# Schematic.net
KiCad netlist of a schematic drawn in Altium Designer
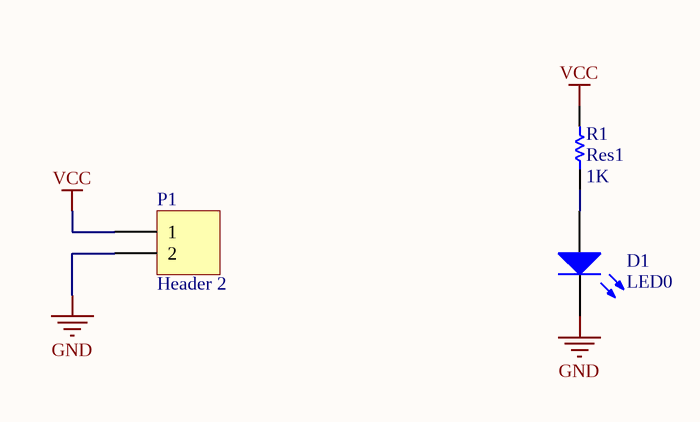
[diagram p0: Schematic.SchDoc]

(export (version "E")
  (design (tool "Eeschema 10.0.6"))
  (components
    (comp (ref "D1")
      (value "LED0")
      (footprint "LED-0")
      (description "Typical INFRARED GaAs LED")
      (fields (field (name "PUBLISHER") "Altium Limited"))
      (libsource (lib "Miscellaneous Devices") (part "LED0"))
    )
    (comp (ref "P1")
      (value "Header 2")
      (footprint "HDR1X2")
      (description "Header, 2-Pin")
      (fields (field (name "PUBLISHER") "Altium Limited"))
      (libsource (lib "Miscellaneous Connectors") (part "Header 2"))
    )
    (comp (ref "R1")
      (value "Res1")
      (footprint "AXIAL-0.3")
      (description "Resistor")
      (fields (field (name "ALTIUM_VALUE") "1K") (field (name "PUBLISHER") "Altium Limited"))
      (libsource (lib "Miscellaneous Devices") (part "Res1"))
    )
  )
  (nets
    (net (code "1") (name "GND") (class "Default")
      (node (ref "D1") (pin "2") (pinfunction "K_2") (pintype "passive"))
      (node (ref "P1") (pin "2") (pinfunction "2_2") (pintype "passive"))
    )
    (net (code "2") (name "Net-(D1-A)") (class "Default")
      (node (ref "D1") (pin "1") (pinfunction "A_1") (pintype "passive"))
      (node (ref "R1") (pin "1") (pinfunction "1_1") (pintype "passive"))
    )
    (net (code "3") (name "VCC") (class "Default")
      (node (ref "P1") (pin "1") (pinfunction "1_1") (pintype "passive"))
      (node (ref "R1") (pin "2") (pinfunction "2_2") (pintype "passive"))
    )
  )
)
